# 1_CONNECTOR.net
KiCad netlist of a schematic drawn in Altium Designer
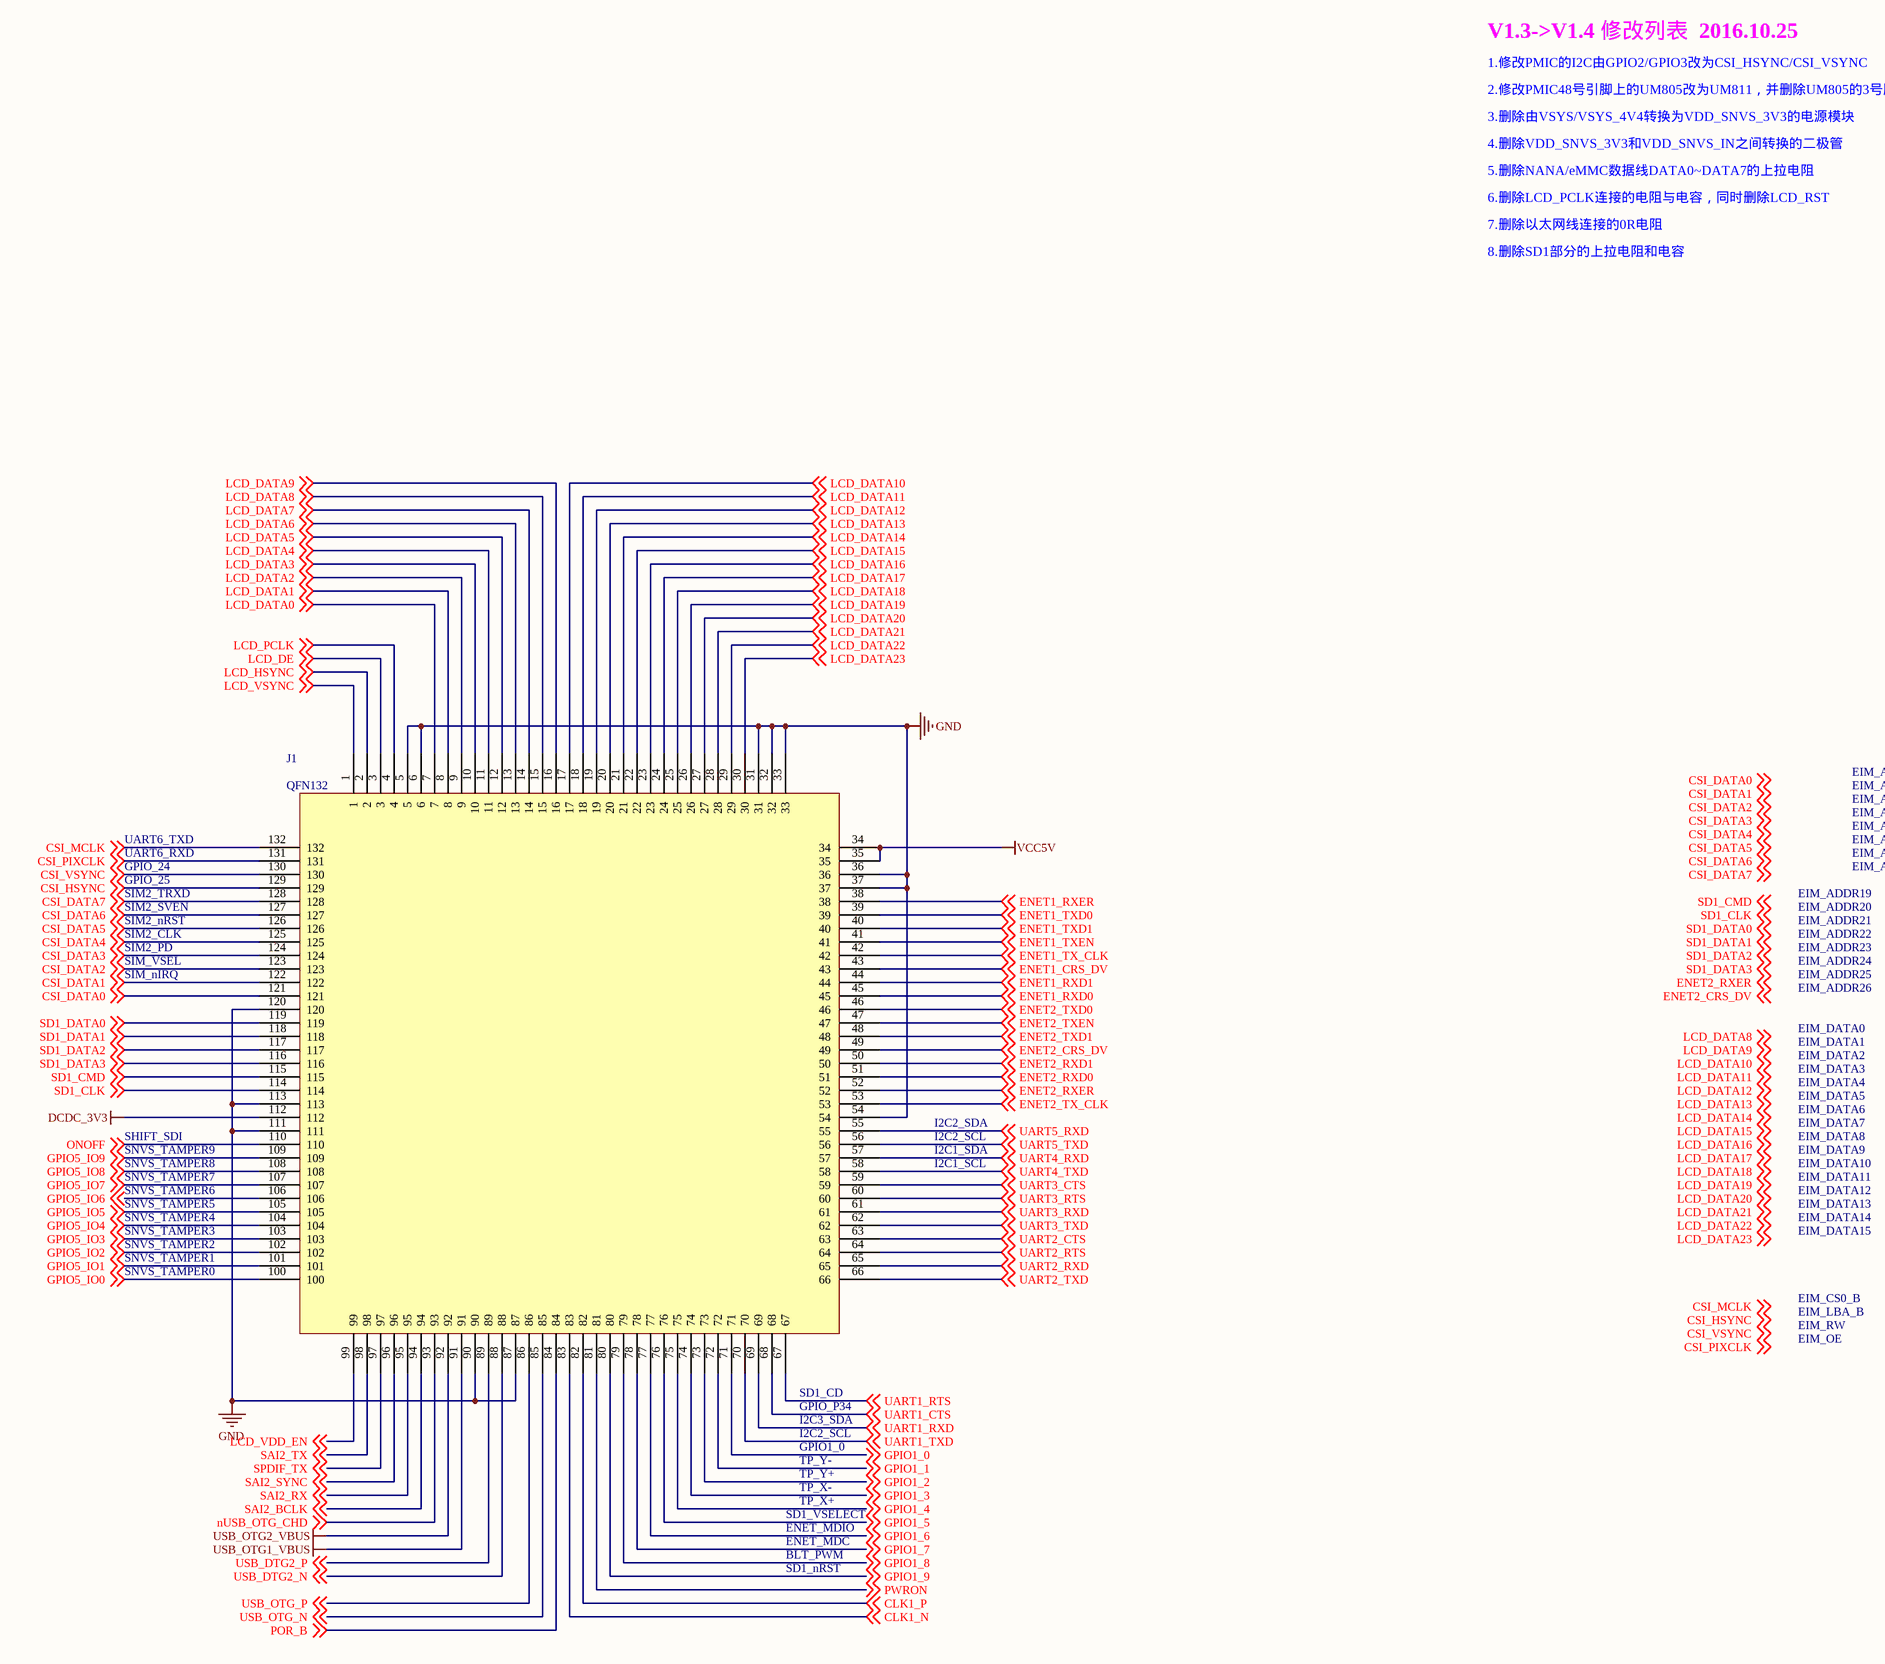
[diagram p0: 1.CONNECTOR.SchDoc]

(export (version "E")
  (design (tool "Eeschema 10.0.6"))
  (components
    (comp (ref "J1")
      (value "QFN132")
      (footprint "MC-IMX6UL-CORE:YPK33X4")
      (libsource (lib "Schlib1") (part "QFN132"))
    )
  )
  (nets
    (net (code "1") (name "CLK1_N") (class "Default")
      (node (ref "J1") (pin "83") (pinfunction "83_83") (pintype "passive"))
    )
    (net (code "2") (name "CLK1_P") (class "Default")
      (node (ref "J1") (pin "82") (pinfunction "82_82") (pintype "passive"))
    )
    (net (code "3") (name "CSI_DATA0") (class "Default")
      (node (ref "J1") (pin "121") (pinfunction "121_121") (pintype "passive"))
    )
    (net (code "4") (name "CSI_DATA1") (class "Default")
      (node (ref "J1") (pin "122") (pinfunction "122_122") (pintype "passive"))
    )
    (net (code "5") (name "CSI_DATA2") (class "Default")
      (node (ref "J1") (pin "123") (pinfunction "123_123") (pintype "passive"))
    )
    (net (code "6") (name "CSI_DATA3") (class "Default")
      (node (ref "J1") (pin "124") (pinfunction "124_124") (pintype "passive"))
    )
    (net (code "7") (name "CSI_DATA4") (class "Default")
      (node (ref "J1") (pin "125") (pinfunction "125_125") (pintype "passive"))
    )
    (net (code "8") (name "CSI_DATA5") (class "Default")
      (node (ref "J1") (pin "126") (pinfunction "126_126") (pintype "passive"))
    )
    (net (code "9") (name "CSI_DATA6") (class "Default")
      (node (ref "J1") (pin "127") (pinfunction "127_127") (pintype "passive"))
    )
    (net (code "10") (name "CSI_DATA7") (class "Default")
      (node (ref "J1") (pin "128") (pinfunction "128_128") (pintype "passive"))
    )
    (net (code "11") (name "CSI_HSYNC") (class "Default")
      (node (ref "J1") (pin "129") (pinfunction "129_129") (pintype "passive"))
    )
    (net (code "12") (name "CSI_MCLK") (class "Default")
      (node (ref "J1") (pin "132") (pinfunction "132_132") (pintype "passive"))
    )
    (net (code "13") (name "CSI_PIXCLK") (class "Default")
      (node (ref "J1") (pin "131") (pinfunction "131_131") (pintype "passive"))
    )
    (net (code "14") (name "CSI_VSYNC") (class "Default")
      (node (ref "J1") (pin "130") (pinfunction "130_130") (pintype "passive"))
    )
    (net (code "15") (name "DCDC_3V3") (class "Default")
      (node (ref "J1") (pin "112") (pinfunction "112_112") (pintype "passive"))
    )
    (net (code "16") (name "ENET1_CRS_DV") (class "Default")
      (node (ref "J1") (pin "43") (pinfunction "43_43") (pintype "passive"))
    )
    (net (code "17") (name "ENET1_RXD0") (class "Default")
      (node (ref "J1") (pin "45") (pinfunction "45_45") (pintype "passive"))
    )
    (net (code "18") (name "ENET1_RXD1") (class "Default")
      (node (ref "J1") (pin "44") (pinfunction "44_44") (pintype "passive"))
    )
    (net (code "19") (name "ENET1_RXER") (class "Default")
      (node (ref "J1") (pin "38") (pinfunction "38_38") (pintype "passive"))
    )
    (net (code "20") (name "ENET1_TXD0") (class "Default")
      (node (ref "J1") (pin "39") (pinfunction "39_39") (pintype "passive"))
    )
    (net (code "21") (name "ENET1_TXD1") (class "Default")
      (node (ref "J1") (pin "40") (pinfunction "40_40") (pintype "passive"))
    )
    (net (code "22") (name "ENET1_TXEN") (class "Default")
      (node (ref "J1") (pin "41") (pinfunction "41_41") (pintype "passive"))
    )
    (net (code "23") (name "ENET1_TX_CLK") (class "Default")
      (node (ref "J1") (pin "42") (pinfunction "42_42") (pintype "passive"))
    )
    (net (code "24") (name "ENET2_CRS_DV") (class "Default")
      (node (ref "J1") (pin "49") (pinfunction "49_49") (pintype "passive"))
    )
    (net (code "25") (name "ENET2_RXD0") (class "Default")
      (node (ref "J1") (pin "51") (pinfunction "51_51") (pintype "passive"))
    )
    (net (code "26") (name "ENET2_RXD1") (class "Default")
      (node (ref "J1") (pin "50") (pinfunction "50_50") (pintype "passive"))
    )
    (net (code "27") (name "ENET2_RXER") (class "Default")
      (node (ref "J1") (pin "52") (pinfunction "52_52") (pintype "passive"))
    )
    (net (code "28") (name "ENET2_TXD0") (class "Default")
      (node (ref "J1") (pin "46") (pinfunction "46_46") (pintype "passive"))
    )
    (net (code "29") (name "ENET2_TXD1") (class "Default")
      (node (ref "J1") (pin "48") (pinfunction "48_48") (pintype "passive"))
    )
    (net (code "30") (name "ENET2_TXEN") (class "Default")
      (node (ref "J1") (pin "47") (pinfunction "47_47") (pintype "passive"))
    )
    (net (code "31") (name "ENET2_TX_CLK") (class "Default")
      (node (ref "J1") (pin "53") (pinfunction "53_53") (pintype "passive"))
    )
    (net (code "32") (name "GND") (class "Default")
      (node (ref "J1") (pin "111") (pinfunction "111_111") (pintype "passive"))
      (node (ref "J1") (pin "113") (pinfunction "113_113") (pintype "passive"))
      (node (ref "J1") (pin "120") (pinfunction "120_120") (pintype "passive"))
      (node (ref "J1") (pin "31") (pinfunction "31_31") (pintype "passive"))
      (node (ref "J1") (pin "32") (pinfunction "32_32") (pintype "passive"))
      (node (ref "J1") (pin "33") (pinfunction "33_33") (pintype "passive"))
      (node (ref "J1") (pin "36") (pinfunction "36_36") (pintype "passive"))
      (node (ref "J1") (pin "37") (pinfunction "37_37") (pintype "passive"))
      (node (ref "J1") (pin "5") (pinfunction "5_5") (pintype "passive"))
      (node (ref "J1") (pin "54") (pinfunction "54_54") (pintype "passive"))
      (node (ref "J1") (pin "6") (pinfunction "6_6") (pintype "passive"))
      (node (ref "J1") (pin "87") (pinfunction "87_87") (pintype "passive"))
      (node (ref "J1") (pin "90") (pinfunction "90_90") (pintype "passive"))
    )
    (net (code "33") (name "GPIO1_0") (class "Default")
      (node (ref "J1") (pin "71") (pinfunction "71_71") (pintype "passive"))
    )
    (net (code "34") (name "GPIO1_1") (class "Default")
      (node (ref "J1") (pin "72") (pinfunction "72_72") (pintype "passive"))
    )
    (net (code "35") (name "GPIO1_2") (class "Default")
      (node (ref "J1") (pin "73") (pinfunction "73_73") (pintype "passive"))
    )
    (net (code "36") (name "GPIO1_3") (class "Default")
      (node (ref "J1") (pin "74") (pinfunction "74_74") (pintype "passive"))
    )
    (net (code "37") (name "GPIO1_4") (class "Default")
      (node (ref "J1") (pin "75") (pinfunction "75_75") (pintype "passive"))
    )
    (net (code "38") (name "GPIO1_5") (class "Default")
      (node (ref "J1") (pin "76") (pinfunction "76_76") (pintype "passive"))
    )
    (net (code "39") (name "GPIO1_6") (class "Default")
      (node (ref "J1") (pin "77") (pinfunction "77_77") (pintype "passive"))
    )
    (net (code "40") (name "GPIO1_7") (class "Default")
      (node (ref "J1") (pin "78") (pinfunction "78_78") (pintype "passive"))
    )
    (net (code "41") (name "GPIO1_8") (class "Default")
      (node (ref "J1") (pin "79") (pinfunction "79_79") (pintype "passive"))
    )
    (net (code "42") (name "GPIO1_9") (class "Default")
      (node (ref "J1") (pin "80") (pinfunction "80_80") (pintype "passive"))
    )
    (net (code "43") (name "GPIO5_IO0") (class "Default")
      (node (ref "J1") (pin "100") (pinfunction "100_100") (pintype "passive"))
    )
    (net (code "44") (name "GPIO5_IO1") (class "Default")
      (node (ref "J1") (pin "101") (pinfunction "101_101") (pintype "passive"))
    )
    (net (code "45") (name "GPIO5_IO2") (class "Default")
      (node (ref "J1") (pin "102") (pinfunction "102_102") (pintype "passive"))
    )
    (net (code "46") (name "GPIO5_IO3") (class "Default")
      (node (ref "J1") (pin "103") (pinfunction "103_103") (pintype "passive"))
    )
    (net (code "47") (name "GPIO5_IO4") (class "Default")
      (node (ref "J1") (pin "104") (pinfunction "104_104") (pintype "passive"))
    )
    (net (code "48") (name "GPIO5_IO5") (class "Default")
      (node (ref "J1") (pin "105") (pinfunction "105_105") (pintype "passive"))
    )
    (net (code "49") (name "GPIO5_IO6") (class "Default")
      (node (ref "J1") (pin "106") (pinfunction "106_106") (pintype "passive"))
    )
    (net (code "50") (name "GPIO5_IO7") (class "Default")
      (node (ref "J1") (pin "107") (pinfunction "107_107") (pintype "passive"))
    )
    (net (code "51") (name "GPIO5_IO8") (class "Default")
      (node (ref "J1") (pin "108") (pinfunction "108_108") (pintype "passive"))
    )
    (net (code "52") (name "GPIO5_IO9") (class "Default")
      (node (ref "J1") (pin "109") (pinfunction "109_109") (pintype "passive"))
    )
    (net (code "53") (name "LCD_DATA0") (class "Default")
      (node (ref "J1") (pin "7") (pinfunction "7_7") (pintype "passive"))
    )
    (net (code "54") (name "LCD_DATA1") (class "Default")
      (node (ref "J1") (pin "8") (pinfunction "8_8") (pintype "passive"))
    )
    (net (code "55") (name "LCD_DATA2") (class "Default")
      (node (ref "J1") (pin "9") (pinfunction "9_9") (pintype "passive"))
    )
    (net (code "56") (name "LCD_DATA3") (class "Default")
      (node (ref "J1") (pin "10") (pinfunction "10_10") (pintype "passive"))
    )
    (net (code "57") (name "LCD_DATA4") (class "Default")
      (node (ref "J1") (pin "11") (pinfunction "11_11") (pintype "passive"))
    )
    (net (code "58") (name "LCD_DATA5") (class "Default")
      (node (ref "J1") (pin "12") (pinfunction "12_12") (pintype "passive"))
    )
    (net (code "59") (name "LCD_DATA6") (class "Default")
      (node (ref "J1") (pin "13") (pinfunction "13_13") (pintype "passive"))
    )
    (net (code "60") (name "LCD_DATA7") (class "Default")
      (node (ref "J1") (pin "14") (pinfunction "14_14") (pintype "passive"))
    )
    (net (code "61") (name "LCD_DATA8") (class "Default")
      (node (ref "J1") (pin "15") (pinfunction "15_15") (pintype "passive"))
    )
    (net (code "62") (name "LCD_DATA9") (class "Default")
      (node (ref "J1") (pin "16") (pinfunction "16_16") (pintype "passive"))
    )
    (net (code "63") (name "LCD_DATA10") (class "Default")
      (node (ref "J1") (pin "17") (pinfunction "17_17") (pintype "passive"))
    )
    (net (code "64") (name "LCD_DATA11") (class "Default")
      (node (ref "J1") (pin "18") (pinfunction "18_18") (pintype "passive"))
    )
    (net (code "65") (name "LCD_DATA12") (class "Default")
      (node (ref "J1") (pin "19") (pinfunction "19_19") (pintype "passive"))
    )
    (net (code "66") (name "LCD_DATA13") (class "Default")
      (node (ref "J1") (pin "20") (pinfunction "20_20") (pintype "passive"))
    )
    (net (code "67") (name "LCD_DATA14") (class "Default")
      (node (ref "J1") (pin "21") (pinfunction "21_21") (pintype "passive"))
    )
    (net (code "68") (name "LCD_DATA15") (class "Default")
      (node (ref "J1") (pin "22") (pinfunction "22_22") (pintype "passive"))
    )
    (net (code "69") (name "LCD_DATA16") (class "Default")
      (node (ref "J1") (pin "23") (pinfunction "23_23") (pintype "passive"))
    )
    (net (code "70") (name "LCD_DATA17") (class "Default")
      (node (ref "J1") (pin "24") (pinfunction "24_24") (pintype "passive"))
    )
    (net (code "71") (name "LCD_DATA18") (class "Default")
      (node (ref "J1") (pin "25") (pinfunction "25_25") (pintype "passive"))
    )
    (net (code "72") (name "LCD_DATA19") (class "Default")
      (node (ref "J1") (pin "26") (pinfunction "26_26") (pintype "passive"))
    )
    (net (code "73") (name "LCD_DATA20") (class "Default")
      (node (ref "J1") (pin "27") (pinfunction "27_27") (pintype "passive"))
    )
    (net (code "74") (name "LCD_DATA21") (class "Default")
      (node (ref "J1") (pin "28") (pinfunction "28_28") (pintype "passive"))
    )
    (net (code "75") (name "LCD_DATA22") (class "Default")
      (node (ref "J1") (pin "29") (pinfunction "29_29") (pintype "passive"))
    )
    (net (code "76") (name "LCD_DATA23") (class "Default")
      (node (ref "J1") (pin "30") (pinfunction "30_30") (pintype "passive"))
    )
    (net (code "77") (name "LCD_DE") (class "Default")
      (node (ref "J1") (pin "3") (pinfunction "3_3") (pintype "passive"))
    )
    (net (code "78") (name "LCD_HSYNC") (class "Default")
      (node (ref "J1") (pin "2") (pinfunction "2_2") (pintype "passive"))
    )
    (net (code "79") (name "LCD_PCLK") (class "Default")
      (node (ref "J1") (pin "4") (pinfunction "4_4") (pintype "passive"))
    )
    (net (code "80") (name "LCD_VDD_EN") (class "Default")
      (node (ref "J1") (pin "99") (pinfunction "99_99") (pintype "passive"))
    )
    (net (code "81") (name "LCD_VSYNC") (class "Default")
      (node (ref "J1") (pin "1") (pinfunction "1_1") (pintype "passive"))
    )
    (net (code "82") (name "ONOFF") (class "Default")
      (node (ref "J1") (pin "110") (pinfunction "110_110") (pintype "passive"))
    )
    (net (code "83") (name "POR_B") (class "Default")
      (node (ref "J1") (pin "84") (pinfunction "84_84") (pintype "passive"))
    )
    (net (code "84") (name "PWRON") (class "Default")
      (node (ref "J1") (pin "81") (pinfunction "81_81") (pintype "passive"))
    )
    (net (code "85") (name "SAI2_BCLK") (class "Default")
      (node (ref "J1") (pin "94") (pinfunction "94_94") (pintype "passive"))
    )
    (net (code "86") (name "SAI2_RX") (class "Default")
      (node (ref "J1") (pin "95") (pinfunction "95_95") (pintype "passive"))
    )
    (net (code "87") (name "SAI2_SYNC") (class "Default")
      (node (ref "J1") (pin "96") (pinfunction "96_96") (pintype "passive"))
    )
    (net (code "88") (name "SAI2_TX") (class "Default")
      (node (ref "J1") (pin "98") (pinfunction "98_98") (pintype "passive"))
    )
    (net (code "89") (name "SD1_CLK") (class "Default")
      (node (ref "J1") (pin "114") (pinfunction "114_114") (pintype "passive"))
    )
    (net (code "90") (name "SD1_CMD") (class "Default")
      (node (ref "J1") (pin "115") (pinfunction "115_115") (pintype "passive"))
    )
    (net (code "91") (name "SD1_DATA0") (class "Default")
      (node (ref "J1") (pin "119") (pinfunction "119_119") (pintype "passive"))
    )
    (net (code "92") (name "SD1_DATA1") (class "Default")
      (node (ref "J1") (pin "118") (pinfunction "118_118") (pintype "passive"))
    )
    (net (code "93") (name "SD1_DATA2") (class "Default")
      (node (ref "J1") (pin "117") (pinfunction "117_117") (pintype "passive"))
    )
    (net (code "94") (name "SD1_DATA3") (class "Default")
      (node (ref "J1") (pin "116") (pinfunction "116_116") (pintype "passive"))
    )
    (net (code "95") (name "SPDIF_TX") (class "Default")
      (node (ref "J1") (pin "97") (pinfunction "97_97") (pintype "passive"))
    )
    (net (code "96") (name "UART1_CTS") (class "Default")
      (node (ref "J1") (pin "68") (pinfunction "68_68") (pintype "passive"))
    )
    (net (code "97") (name "UART1_RTS") (class "Default")
      (node (ref "J1") (pin "67") (pinfunction "67_67") (pintype "passive"))
    )
    (net (code "98") (name "UART1_RXD") (class "Default")
      (node (ref "J1") (pin "69") (pinfunction "69_69") (pintype "passive"))
    )
    (net (code "99") (name "UART1_TXD") (class "Default")
      (node (ref "J1") (pin "70") (pinfunction "70_70") (pintype "passive"))
    )
    (net (code "100") (name "UART2_CTS") (class "Default")
      (node (ref "J1") (pin "63") (pinfunction "63_63") (pintype "passive"))
    )
    (net (code "101") (name "UART2_RTS") (class "Default")
      (node (ref "J1") (pin "64") (pinfunction "64_64") (pintype "passive"))
    )
    (net (code "102") (name "UART2_RXD") (class "Default")
      (node (ref "J1") (pin "65") (pinfunction "65_65") (pintype "passive"))
    )
    (net (code "103") (name "UART2_TXD") (class "Default")
      (node (ref "J1") (pin "66") (pinfunction "66_66") (pintype "passive"))
    )
    (net (code "104") (name "UART3_CTS") (class "Default")
      (node (ref "J1") (pin "59") (pinfunction "59_59") (pintype "passive"))
    )
    (net (code "105") (name "UART3_RTS") (class "Default")
      (node (ref "J1") (pin "60") (pinfunction "60_60") (pintype "passive"))
    )
    (net (code "106") (name "UART3_RXD") (class "Default")
      (node (ref "J1") (pin "61") (pinfunction "61_61") (pintype "passive"))
    )
    (net (code "107") (name "UART3_TXD") (class "Default")
      (node (ref "J1") (pin "62") (pinfunction "62_62") (pintype "passive"))
    )
    (net (code "108") (name "UART4_RXD") (class "Default")
      (node (ref "J1") (pin "57") (pinfunction "57_57") (pintype "passive"))
    )
    (net (code "109") (name "UART4_TXD") (class "Default")
      (node (ref "J1") (pin "58") (pinfunction "58_58") (pintype "passive"))
    )
    (net (code "110") (name "UART5_RXD") (class "Default")
      (node (ref "J1") (pin "55") (pinfunction "55_55") (pintype "passive"))
    )
    (net (code "111") (name "UART5_TXD") (class "Default")
      (node (ref "J1") (pin "56") (pinfunction "56_56") (pintype "passive"))
    )
    (net (code "112") (name "USB_DTG2_N") (class "Default")
      (node (ref "J1") (pin "88") (pinfunction "88_88") (pintype "passive"))
    )
    (net (code "113") (name "USB_DTG2_P") (class "Default")
      (node (ref "J1") (pin "89") (pinfunction "89_89") (pintype "passive"))
    )
    (net (code "114") (name "USB_OTG1_VBUS") (class "Default")
      (node (ref "J1") (pin "91") (pinfunction "91_91") (pintype "passive"))
    )
    (net (code "115") (name "USB_OTG2_VBUS") (class "Default")
      (node (ref "J1") (pin "92") (pinfunction "92_92") (pintype "passive"))
    )
    (net (code "116") (name "USB_OTG_N") (class "Default")
      (node (ref "J1") (pin "85") (pinfunction "85_85") (pintype "passive"))
    )
    (net (code "117") (name "USB_OTG_P") (class "Default")
      (node (ref "J1") (pin "86") (pinfunction "86_86") (pintype "passive"))
    )
    (net (code "118") (name "VCC5V") (class "Default")
      (node (ref "J1") (pin "34") (pinfunction "34_34") (pintype "passive"))
      (node (ref "J1") (pin "35") (pinfunction "35_35") (pintype "passive"))
    )
    (net (code "119") (name "nUSB_OTG_CHD") (class "Default")
      (node (ref "J1") (pin "93") (pinfunction "93_93") (pintype "passive"))
    )
  )
)
